# LC_LPF7.net
KiCad netlist of a schematic drawn in Altium Designer
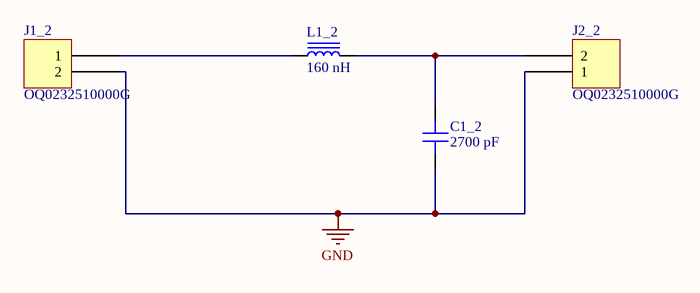
[diagram p0: LC_LPF7.SchDoc]

(export (version "E")
  (design (tool "Eeschema 10.0.6"))
  (components
    (comp (ref "C1_2")
      (value "2700 pF")
      (footprint "CAP 0603_1608")
      (description "CAP CER 2700PF 25V NP0 0603")
      (fields (field (name "PART NUMBER") "C0603C272F3GAC7867") (field (name "MANUFACTURER") "KEMET"))
      (libsource (lib "Celestial Altium Library - altium_library") (part "Capacitor"))
    )
    (comp (ref "J1_2")
      (value "OQ0232510000G")
      (footprint "FCI 06-381-2PIN")
      (description "TERM BLOCK HDR 2POS 90DEG 3.81MM")
      (fields (field (name "MANUFACTURER") "Amphenol Anytek"))
      (libsource (lib "") (part "2 Pin_1"))
    )
    (comp (ref "J2_2")
      (value "OQ0232510000G")
      (footprint "FCI 06-381-2PIN")
      (description "TERM BLOCK HDR 2POS 90DEG 3.81MM")
      (fields (field (name "MANUFACTURER") "Amphenol Anytek"))
      (libsource (lib "Celestial Altium Library - altium_library") (part "2 Pin"))
    )
    (comp (ref "L1_2")
      (value "160 nH")
      (footprint "IND 0402_1005 RF WW")
      (description "FIXED IND 160NH 480MA 330MOHM SM")
      (fields
        (field (name "PART NUMBER") "LQW15CNR16J00D")
        (field (name "MANUFACTURER") "Murata Electronics")
      )
      (libsource (lib "Celestial Altium Library - altium_library") (part "Inductor"))
    )
  )
  (nets
    (net (code "1") (name "GND") (class "Default")
      (node (ref "C1_2") (pin "1") (pinfunction "1_1") (pintype "passive"))
      (node (ref "J1_2") (pin "2") (pinfunction "2_2") (pintype "passive"))
      (node (ref "J2_2") (pin "1") (pinfunction "1_1") (pintype "passive"))
    )
    (net (code "2") (name "Net-(C1_2-Pad2)") (class "Default")
      (node (ref "C1_2") (pin "2") (pinfunction "2_2") (pintype "passive"))
      (node (ref "J2_2") (pin "2") (pinfunction "2_2") (pintype "passive"))
      (node (ref "L1_2") (pin "2") (pinfunction "2_2") (pintype "passive"))
    )
    (net (code "3") (name "Net-(J1_2-Pad1)") (class "Default")
      (node (ref "J1_2") (pin "1") (pinfunction "1_1") (pintype "passive"))
      (node (ref "L1_2") (pin "1") (pinfunction "1_1") (pintype "passive"))
    )
  )
)
